# IPS_PilotCape.net
KiCad netlist of a schematic drawn in EAGLE
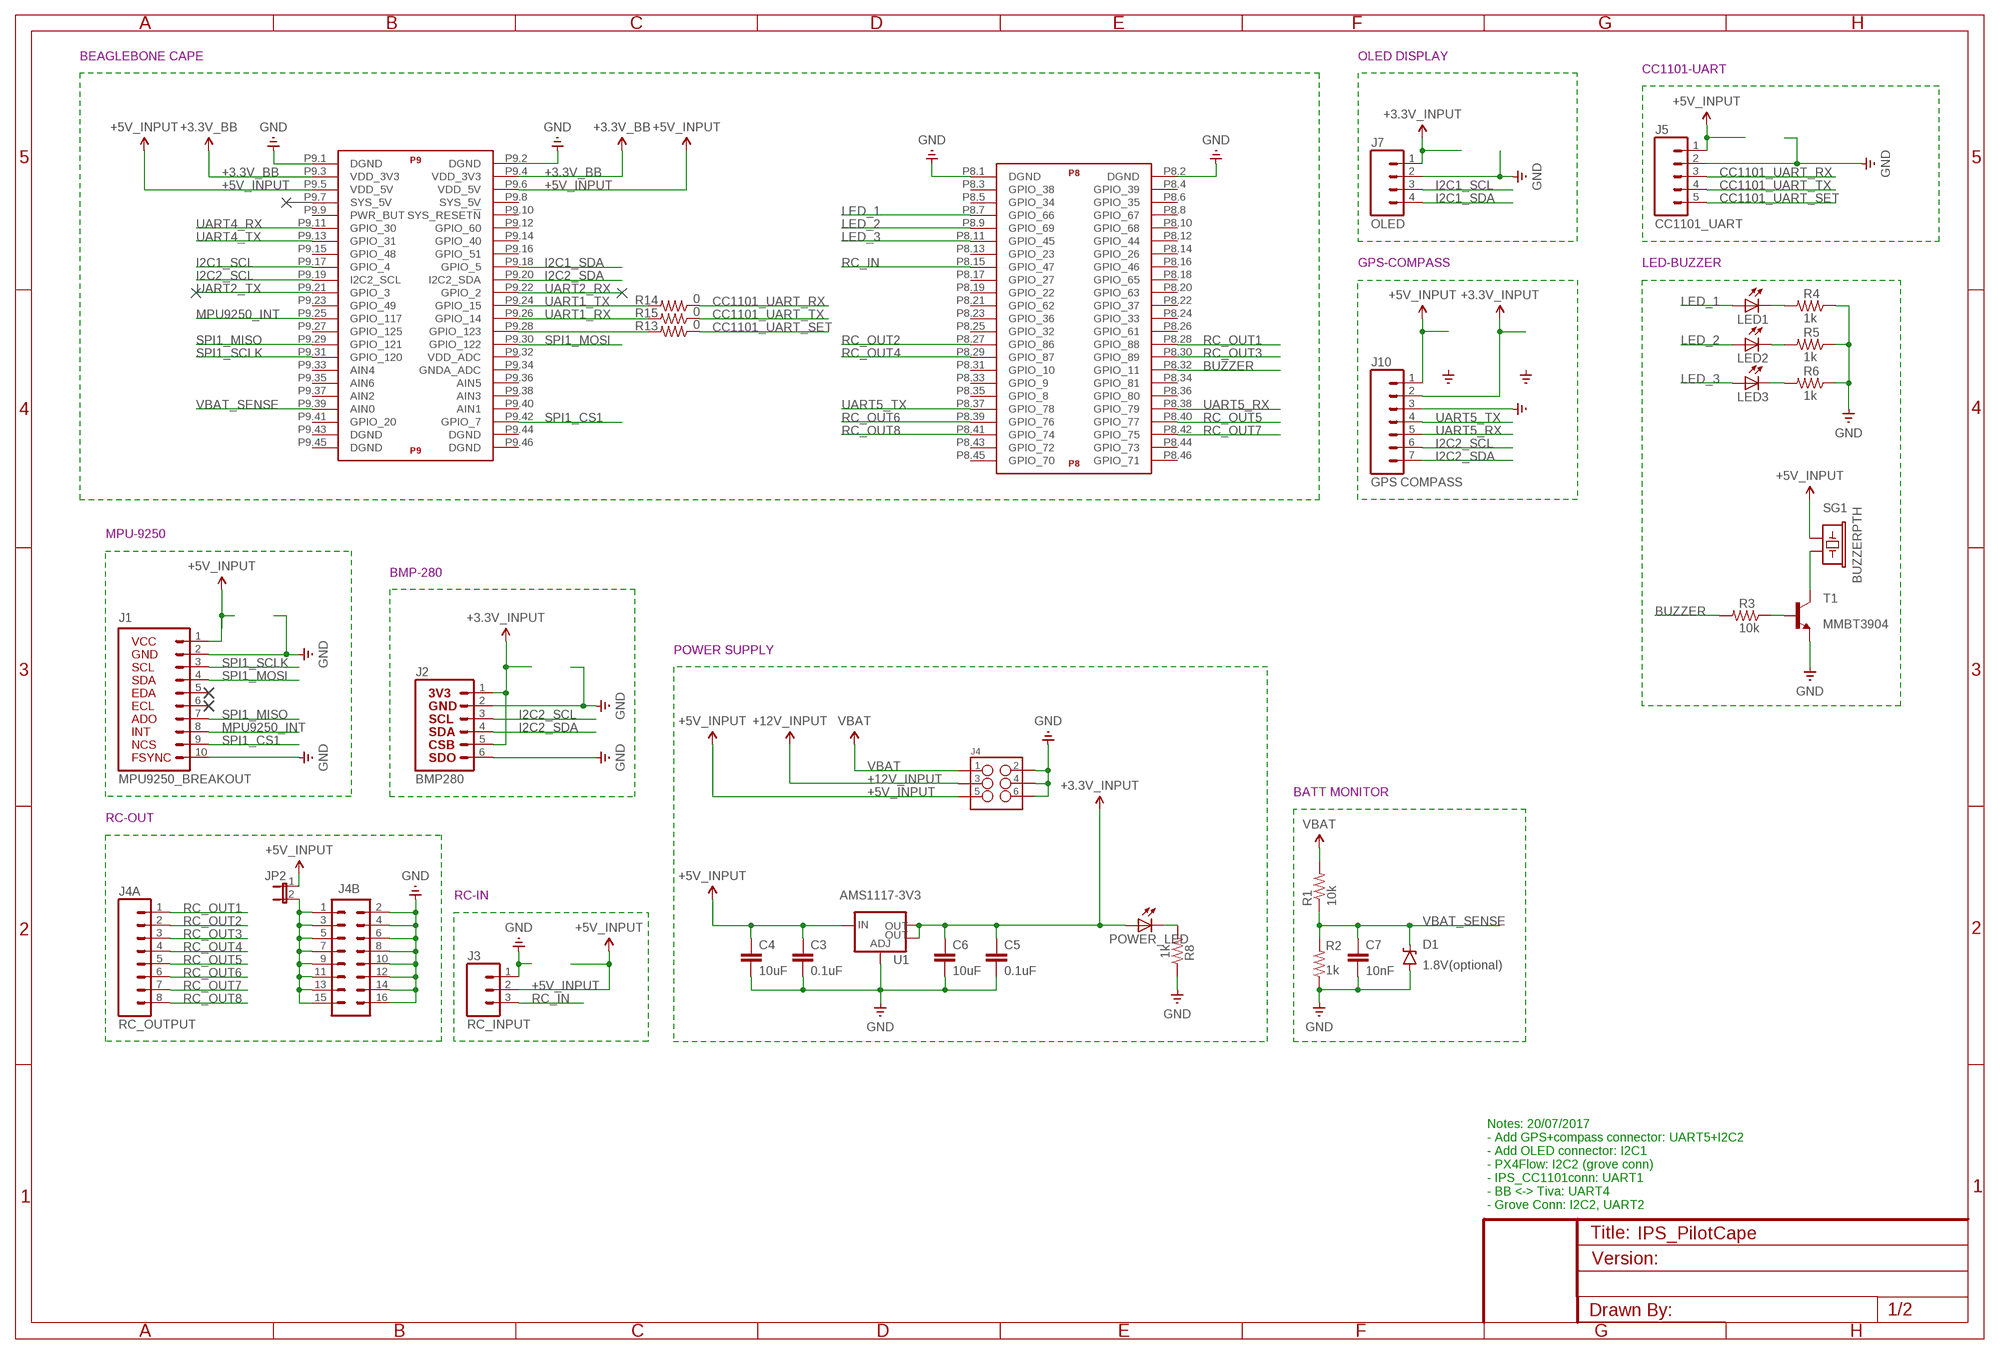
[diagram p0: schematic, sheet 1]
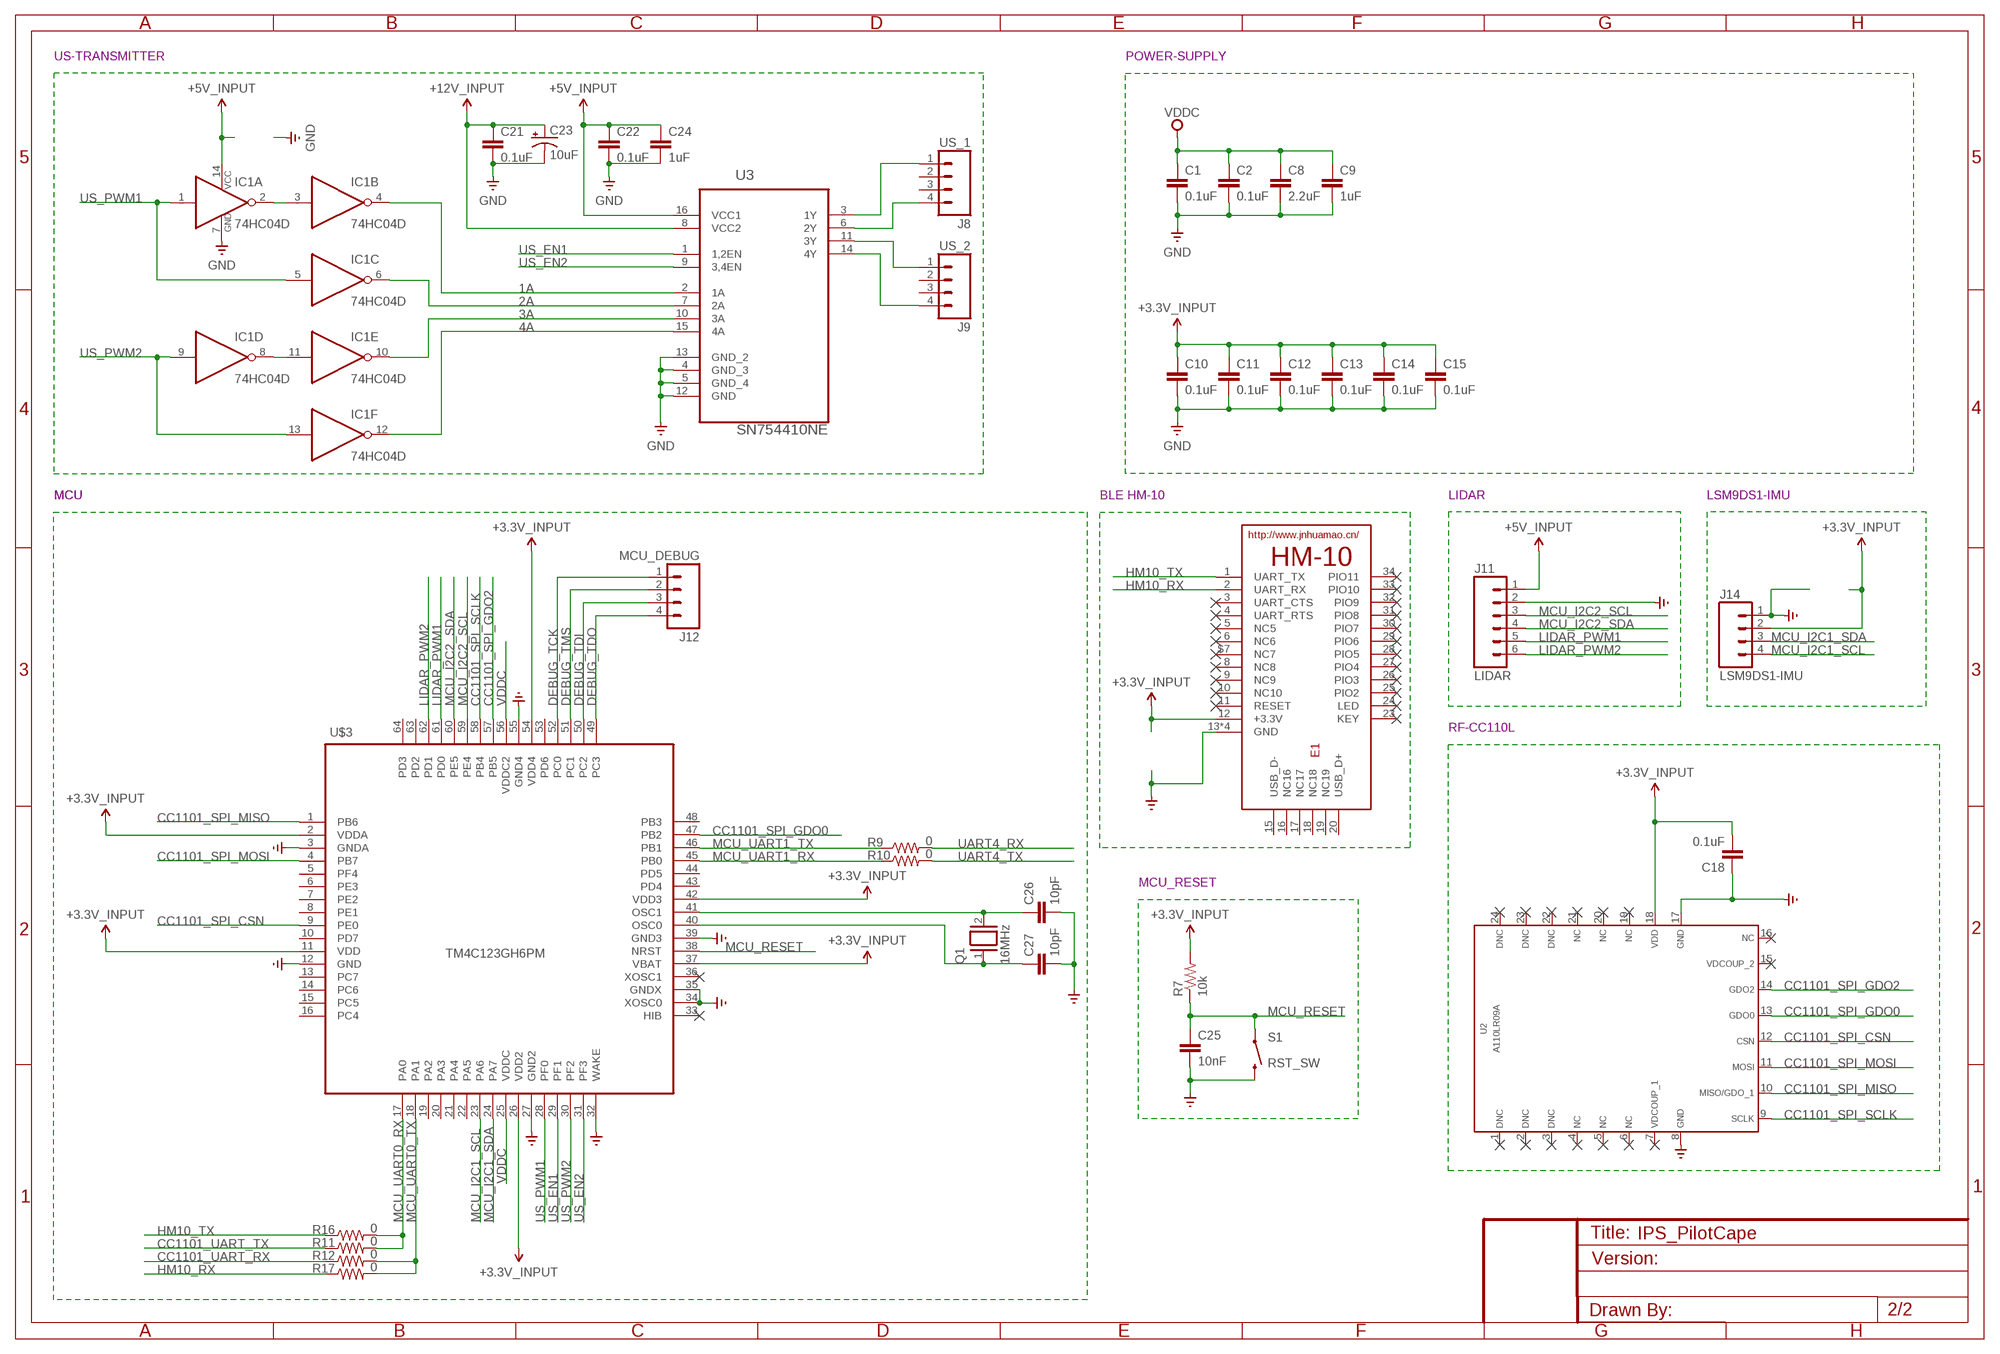
[diagram p1: schematic, sheet 2]

(export (version "E")
  (design (tool "Eeschema 10.0.6"))
  (components
    (comp (ref "C1")
      (value "0.1uF")
      (footprint "eagle-import:0603-CAP")
      (libsource (lib "eagle-import") (part "CAP0603-CAP"))
    )
    (comp (ref "C2")
      (value "0.1uF")
      (footprint "eagle-import:0603-CAP")
      (libsource (lib "eagle-import") (part "CAP0603-CAP"))
    )
    (comp (ref "C8")
      (value "2.2uF")
      (footprint "eagle-import:0603-CAP")
      (libsource (lib "eagle-import") (part "CAP0603-CAP"))
    )
    (comp (ref "C9")
      (value "1uF")
      (footprint "eagle-import:0603-CAP")
      (libsource (lib "eagle-import") (part "CAP0603-CAP"))
    )
    (comp (ref "C10")
      (value "0.1uF")
      (footprint "eagle-import:0603-CAP")
      (libsource (lib "eagle-import") (part "CAP0603-CAP"))
    )
    (comp (ref "C11")
      (value "0.1uF")
      (footprint "eagle-import:0603-CAP")
      (libsource (lib "eagle-import") (part "CAP0603-CAP"))
    )
    (comp (ref "C12")
      (value "0.1uF")
      (footprint "eagle-import:0603-CAP")
      (libsource (lib "eagle-import") (part "CAP0603-CAP"))
    )
    (comp (ref "C13")
      (value "0.1uF")
      (footprint "eagle-import:0603-CAP")
      (libsource (lib "eagle-import") (part "CAP0603-CAP"))
    )
    (comp (ref "C14")
      (value "0.1uF")
      (footprint "eagle-import:0603-CAP")
      (libsource (lib "eagle-import") (part "CAP0603-CAP"))
    )
    (comp (ref "C15")
      (value "0.1uF")
      (footprint "eagle-import:0603-CAP")
      (libsource (lib "eagle-import") (part "CAP0603-CAP"))
    )
    (comp (ref "C18")
      (value "0.1uF")
      (footprint "eagle-import:0603-CAP")
      (libsource (lib "eagle-import") (part "CAP0603-CAP"))
    )
    (comp (ref "C21")
      (value "0.1uF")
      (footprint "eagle-import:0603-CAP")
      (libsource (lib "eagle-import") (part "CAP0603-CAP"))
    )
    (comp (ref "C22")
      (value "0.1uF")
      (footprint "eagle-import:0603-CAP")
      (libsource (lib "eagle-import") (part "CAP0603-CAP"))
    )
    (comp (ref "C23")
      (value "10uF")
      (footprint "eagle-import:EIA3216")
      (libsource (lib "eagle-import") (part "10UF-16V-10%(TANT)"))
    )
    (comp (ref "C24")
      (value "1uF")
      (footprint "eagle-import:0603-CAP")
      (libsource (lib "eagle-import") (part "CAP0603-CAP"))
    )
    (comp (ref "C25")
      (value "10nF")
      (footprint "eagle-import:0603-CAP")
      (libsource (lib "eagle-import") (part "CAP0603-CAP"))
    )
    (comp (ref "C26")
      (value "10pF")
      (footprint "eagle-import:0603-CAP")
      (libsource (lib "eagle-import") (part "CAP0603-CAP"))
    )
    (comp (ref "C27")
      (value "10pF")
      (footprint "eagle-import:0603-CAP")
      (libsource (lib "eagle-import") (part "CAP0603-CAP"))
    )
    (comp (ref "E1")
      (value "HM-10-BOARD")
      (footprint "eagle-import:26.9X13X2.2_BOARD")
      (libsource (lib "eagle-import") (part "HM-10-BOARD"))
    )
    (comp (ref "IC1")
      (value "74HC04D")
      (footprint "eagle-import:SO14")
      (libsource (lib "eagle-import") (part "7404DHC"))
    )
    (comp (ref "J8")
      (value "US_1")
      (footprint "eagle-import:1X04")
      (libsource (lib "eagle-import") (part "M04PTH"))
    )
    (comp (ref "J9")
      (value "US_2")
      (footprint "eagle-import:1X04")
      (libsource (lib "eagle-import") (part "M04PTH"))
    )
    (comp (ref "J11")
      (value "LIDAR")
      (footprint "eagle-import:1X06")
      (libsource (lib "eagle-import") (part "M06SILK_FEMALE_PTH"))
    )
    (comp (ref "J12")
      (value "MCU_DEBUG")
      (footprint "eagle-import:1X04")
      (libsource (lib "eagle-import") (part "M04PTH"))
    )
    (comp (ref "J14")
      (value "LSM9DS1-IMU")
      (footprint "eagle-import:1X04")
      (libsource (lib "eagle-import") (part "M04PTH"))
    )
    (comp (ref "Q1")
      (value "16MHz")
      (footprint "eagle-import:QS")
      (libsource (lib "eagle-import") (part "XTAL/S"))
    )
    (comp (ref "R7")
      (value "10k")
      (footprint "eagle-import:R0603")
      (libsource (lib "eagle-import") (part "R-US_R0603"))
    )
    (comp (ref "R9")
      (value "0")
      (footprint "eagle-import:R0603")
      (libsource (lib "eagle-import") (part "R-US_R0603"))
    )
    (comp (ref "R10")
      (value "0")
      (footprint "eagle-import:R0603")
      (libsource (lib "eagle-import") (part "R-US_R0603"))
    )
    (comp (ref "R11")
      (value "0")
      (footprint "eagle-import:R0603")
      (libsource (lib "eagle-import") (part "R-US_R0603"))
    )
    (comp (ref "R12")
      (value "0")
      (footprint "eagle-import:R0603")
      (libsource (lib "eagle-import") (part "R-US_R0603"))
    )
    (comp (ref "R16")
      (value "0")
      (footprint "eagle-import:R0603")
      (libsource (lib "eagle-import") (part "R-US_R0603"))
    )
    (comp (ref "R17")
      (value "0")
      (footprint "eagle-import:R0603")
      (libsource (lib "eagle-import") (part "R-US_R0603"))
    )
    (comp (ref "S1")
      (value "RST_SW")
      (footprint "eagle-import:TACTILE-SWITCH-1101NE")
      (libsource (lib "eagle-import") (part "SWITCH-MOMENTARY-2SMD-1101NE"))
    )
    (comp (ref "U$3")
      (value "TM4C123GH6PM")
      (footprint "eagle-import:LQPF-64")
      (libsource (lib "eagle-import") (part "TM4C123GH6PM"))
    )
    (comp (ref "U2")
      (value "A110LR09A")
      (footprint "eagle-import:A110LR09A")
      (libsource (lib "eagle-import") (part "A110LR09A"))
    )
    (comp (ref "U3")
      (value "SN754410NE")
      (footprint "eagle-import:DIP254P762X508-16")
      (libsource (lib "eagle-import") (part "SN754410NE"))
    )
    (comp (ref "C3")
      (value "0.1uF")
      (footprint "eagle-import:0603-CAP")
      (libsource (lib "eagle-import") (part "CAP0603-CAP"))
    )
    (comp (ref "C4")
      (value "10uF")
      (footprint "eagle-import:1210")
      (libsource (lib "eagle-import") (part "SparkFun-Passives_CAP1210"))
    )
    (comp (ref "C5")
      (value "0.1uF")
      (footprint "eagle-import:0603-CAP")
      (libsource (lib "eagle-import") (part "CAP0603-CAP"))
    )
    (comp (ref "C6")
      (value "10uF")
      (footprint "eagle-import:1210")
      (libsource (lib "eagle-import") (part "SparkFun-Passives_CAP1210"))
    )
    (comp (ref "C7")
      (value "10nF")
      (footprint "eagle-import:0603-CAP")
      (libsource (lib "eagle-import") (part "CAP0603-CAP"))
    )
    (comp (ref "D1")
      (value "1.8V(optional)")
      (footprint "eagle-import:SOD-323")
      (libsource (lib "eagle-import") (part "DIODE-ZENER3.3V"))
    )
    (comp (ref "J1")
      (value "MPU9250_BREAKOUT")
      (footprint "eagle-import:MPU9250_BREAKOUT")
      (libsource (lib "eagle-import") (part "MPU9250_BREAKOUT"))
    )
    (comp (ref "J2")
      (value "BMP280")
      (footprint "eagle-import:BMP280")
      (libsource (lib "eagle-import") (part "BMP280"))
    )
    (comp (ref "J3")
      (value "RC_INPUT")
      (footprint "eagle-import:1X03")
      (libsource (lib "eagle-import") (part "M03PTH"))
    )
    (comp (ref "J4")
      (value "M03X2NO_SILK")
      (footprint "eagle-import:2X3-NS")
      (libsource (lib "eagle-import") (part "M03X2NO_SILK"))
    )
    (comp (ref "J4A")
      (value "RC_OUTPUT")
      (footprint "eagle-import:1X08")
      (libsource (lib "eagle-import") (part "M08SILK_FEMALE_PTH"))
    )
    (comp (ref "J4B")
      (value "M08X2")
      (footprint "eagle-import:2X8")
      (libsource (lib "eagle-import") (part "M08X2"))
    )
    (comp (ref "J5")
      (value "CC1101_UART")
      (footprint "eagle-import:1X05")
      (libsource (lib "eagle-import") (part "M05PTH"))
    )
    (comp (ref "J7")
      (value "OLED")
      (footprint "eagle-import:1X04")
      (libsource (lib "eagle-import") (part "M04PTH"))
    )
    (comp (ref "J10")
      (value "GPS COMPASS")
      (footprint "eagle-import:1X07")
      (libsource (lib "eagle-import") (part "M07"))
    )
    (comp (ref "JP2")
      (value "JUMPER-2PTH")
      (footprint "eagle-import:1X02")
      (libsource (lib "eagle-import") (part "JUMPER-2PTH"))
    )
    (comp (ref "LED1")
      (value "LEDCHIPLED_0805")
      (footprint "eagle-import:CHIPLED_0805")
      (libsource (lib "eagle-import") (part "LEDCHIPLED_0805"))
    )
    (comp (ref "LED2")
      (value "LEDCHIPLED_0805")
      (footprint "eagle-import:CHIPLED_0805")
      (libsource (lib "eagle-import") (part "LEDCHIPLED_0805"))
    )
    (comp (ref "LED3")
      (value "LEDCHIPLED_0805")
      (footprint "eagle-import:CHIPLED_0805")
      (libsource (lib "eagle-import") (part "LEDCHIPLED_0805"))
    )
    (comp (ref "POWER_LED")
      (value "LEDCHIPLED_0805")
      (footprint "eagle-import:CHIPLED_0805")
      (libsource (lib "eagle-import") (part "LEDCHIPLED_0805"))
    )
    (comp (ref "R1")
      (value "10k")
      (footprint "eagle-import:R0603")
      (libsource (lib "eagle-import") (part "R-US_R0603"))
    )
    (comp (ref "R2")
      (value "1k")
      (footprint "eagle-import:R0603")
      (libsource (lib "eagle-import") (part "R-US_R0603"))
    )
    (comp (ref "R3")
      (value "10k")
      (footprint "eagle-import:R0603")
      (libsource (lib "eagle-import") (part "R-US_R0603"))
    )
    (comp (ref "R4")
      (value "1k")
      (footprint "eagle-import:R0603")
      (libsource (lib "eagle-import") (part "R-US_R0603"))
    )
    (comp (ref "R5")
      (value "1k")
      (footprint "eagle-import:R0603")
      (libsource (lib "eagle-import") (part "R-US_R0603"))
    )
    (comp (ref "R6")
      (value "1k")
      (footprint "eagle-import:R0603")
      (libsource (lib "eagle-import") (part "R-US_R0603"))
    )
    (comp (ref "R8")
      (value "1k")
      (footprint "eagle-import:R0603")
      (libsource (lib "eagle-import") (part "R-US_R0603"))
    )
    (comp (ref "R13")
      (value "0")
      (footprint "eagle-import:R0603")
      (libsource (lib "eagle-import") (part "R-US_R0603"))
    )
    (comp (ref "R14")
      (value "0")
      (footprint "eagle-import:R0603")
      (libsource (lib "eagle-import") (part "R-US_R0603"))
    )
    (comp (ref "R15")
      (value "0")
      (footprint "eagle-import:R0603")
      (libsource (lib "eagle-import") (part "R-US_R0603"))
    )
    (comp (ref "SG1")
      (value "BUZZERPTH")
      (footprint "eagle-import:BUZZER-12MM")
      (libsource (lib "eagle-import") (part "BUZZERPTH"))
    )
    (comp (ref "T1")
      (value "MMBT3904")
      (footprint "eagle-import:SOT23-BEC")
      (libsource (lib "eagle-import") (part "-NPN-SOT23-BECMMBT3904LT1"))
    )
    (comp (ref "U$2")
      (value "BEAGLE_BONE_BLACK_CAPE")
      (footprint "eagle-import:BEAGLE_BONE_BLACK_CAPE")
      (libsource (lib "eagle-import") (part "BEAGLE_BONE_BLACK_CAPE"))
    )
    (comp (ref "U1")
      (value "AMS1117-3V3")
      (footprint "eagle-import:SOT223")
      (libsource (lib "eagle-import") (part "V_REG_LM1117SOT223"))
    )
  )
  (nets
    (net (code "1") (name "+3.3V_BB") (class "Default")
      (node (ref "U$2") (pin "P9.3") (pinfunction "VDD_3V3_P9.3") (pintype "bidirectional"))
      (node (ref "U$2") (pin "P9.4") (pinfunction "VDD_3V3_P9.4") (pintype "bidirectional"))
    )
    (net (code "2") (name "+3.3V_INPUT") (class "Default")
      (node (ref "C10") (pin "1") (pinfunction "1_1") (pintype "passive"))
      (node (ref "C11") (pin "1") (pinfunction "1_1") (pintype "passive"))
      (node (ref "C12") (pin "1") (pinfunction "1_1") (pintype "passive"))
      (node (ref "C13") (pin "1") (pinfunction "1_1") (pintype "passive"))
      (node (ref "C14") (pin "1") (pinfunction "1_1") (pintype "passive"))
      (node (ref "C15") (pin "1") (pinfunction "1_1") (pintype "passive"))
      (node (ref "C18") (pin "2") (pinfunction "2_2") (pintype "passive"))
      (node (ref "C5") (pin "1") (pinfunction "1_1") (pintype "passive"))
      (node (ref "C6") (pin "1") (pinfunction "1_1") (pintype "passive"))
      (node (ref "E1") (pin "12") (pinfunction "+3.3V_12") (pintype "bidirectional"))
      (node (ref "J10") (pin "2") (pinfunction "2_2") (pintype "passive"))
      (node (ref "J14") (pin "2") (pinfunction "2_2") (pintype "passive"))
      (node (ref "J2") (pin "1") (pinfunction "1_1") (pintype "passive"))
      (node (ref "J2") (pin "5") (pinfunction "5_5") (pintype "passive"))
      (node (ref "J7") (pin "1") (pinfunction "1_1") (pintype "passive"))
      (node (ref "POWER_LED") (pin "A") (pinfunction "A_A") (pintype "passive"))
      (node (ref "R7") (pin "2") (pinfunction "2_2") (pintype "passive"))
      (node (ref "U$3") (pin "11") (pinfunction "VDD_11") (pintype "bidirectional"))
      (node (ref "U$3") (pin "2") (pinfunction "VDDA_2") (pintype "bidirectional"))
      (node (ref "U$3") (pin "26") (pinfunction "VDD2_26") (pintype "bidirectional"))
      (node (ref "U$3") (pin "37") (pinfunction "VBAT_37") (pintype "bidirectional"))
      (node (ref "U$3") (pin "42") (pinfunction "VDD3_42") (pintype "bidirectional"))
      (node (ref "U$3") (pin "54") (pinfunction "VDD4_54") (pintype "bidirectional"))
      (node (ref "U1") (pin "2") (pinfunction "OUT_2") (pintype "output"))
      (node (ref "U1") (pin "4") (pinfunction "OUT_4") (pintype "output"))
      (node (ref "U2") (pin "18") (pinfunction "P$18_18") (pintype "bidirectional"))
    )
    (net (code "3") (name "+5V_INPUT") (class "Default")
      (node (ref "C22") (pin "1") (pinfunction "1_1") (pintype "passive"))
      (node (ref "C24") (pin "1") (pinfunction "1_1") (pintype "passive"))
      (node (ref "C3") (pin "1") (pinfunction "1_1") (pintype "passive"))
      (node (ref "C4") (pin "1") (pinfunction "1_1") (pintype "passive"))
      (node (ref "IC1") (pin "14") (pinfunction "VCC_14") (pintype "power_in"))
      (node (ref "J1") (pin "1") (pinfunction "1_1") (pintype "passive"))
      (node (ref "J10") (pin "1") (pinfunction "1_1") (pintype "passive"))
      (node (ref "J11") (pin "1") (pinfunction "1_1") (pintype "passive"))
      (node (ref "J3") (pin "2") (pinfunction "2_2") (pintype "passive"))
      (node (ref "J4") (pin "5") (pinfunction "5_5") (pintype "bidirectional"))
      (node (ref "J5") (pin "1") (pinfunction "1_1") (pintype "passive"))
      (node (ref "JP2") (pin "1") (pinfunction "1_1") (pintype "passive"))
      (node (ref "SG1") (pin "+") (pinfunction "1_+") (pintype "passive"))
      (node (ref "U$2") (pin "P9.5") (pinfunction "VDD_5V_P9.5") (pintype "bidirectional"))
      (node (ref "U$2") (pin "P9.6") (pinfunction "VDD_5V_P9.6") (pintype "bidirectional"))
      (node (ref "U1") (pin "3") (pinfunction "IN_3") (pintype "input"))
      (node (ref "U3") (pin "16") (pinfunction "VCC1_16") (pintype "power_in"))
    )
    (net (code "4") (name "+12V_INPUT") (class "Default")
      (node (ref "C21") (pin "1") (pinfunction "1_1") (pintype "passive"))
      (node (ref "C23") (pin "A") (pinfunction "+_A") (pintype "passive"))
      (node (ref "J4") (pin "3") (pinfunction "3_3") (pintype "bidirectional"))
      (node (ref "U3") (pin "8") (pinfunction "VCC2_8") (pintype "power_in"))
    )
    (net (code "5") (name "1A") (class "Default")
      (node (ref "IC1") (pin "4") (pinfunction "O_4") (pintype "output"))
      (node (ref "U3") (pin "2") (pinfunction "1A_2") (pintype "input"))
    )
    (net (code "6") (name "2A") (class "Default")
      (node (ref "IC1") (pin "6") (pinfunction "O_6") (pintype "output"))
      (node (ref "U3") (pin "7") (pinfunction "2A_7") (pintype "input"))
    )
    (net (code "7") (name "3A") (class "Default")
      (node (ref "IC1") (pin "10") (pinfunction "O_10") (pintype "output"))
      (node (ref "U3") (pin "10") (pinfunction "3A_10") (pintype "input"))
    )
    (net (code "8") (name "4A") (class "Default")
      (node (ref "IC1") (pin "12") (pinfunction "O_12") (pintype "output"))
      (node (ref "U3") (pin "15") (pinfunction "4A_15") (pintype "input"))
    )
    (net (code "9") (name "BUZZER") (class "Default")
      (node (ref "R3") (pin "2") (pinfunction "2_2") (pintype "passive"))
      (node (ref "U$2") (pin "P8.32") (pinfunction "GPIO_11_P8.32") (pintype "bidirectional"))
    )
    (net (code "10") (name "CC1101_SPI_CSN") (class "Default")
      (node (ref "U$3") (pin "9") (pinfunction "PE0_9") (pintype "bidirectional"))
      (node (ref "U2") (pin "12") (pinfunction "P$12_12") (pintype "bidirectional"))
    )
    (net (code "11") (name "CC1101_SPI_GDO0") (class "Default")
      (node (ref "U$3") (pin "47") (pinfunction "PB2_47") (pintype "bidirectional"))
      (node (ref "U2") (pin "13") (pinfunction "P$13_13") (pintype "bidirectional"))
    )
    (net (code "12") (name "CC1101_SPI_GDO2") (class "Default")
      (node (ref "U$3") (pin "57") (pinfunction "PB5_57") (pintype "bidirectional"))
      (node (ref "U2") (pin "14") (pinfunction "P$14_14") (pintype "bidirectional"))
    )
    (net (code "13") (name "CC1101_SPI_MISO") (class "Default")
      (node (ref "U$3") (pin "1") (pinfunction "PB6_1") (pintype "bidirectional"))
      (node (ref "U2") (pin "10") (pinfunction "P$10_10") (pintype "bidirectional"))
    )
    (net (code "14") (name "CC1101_SPI_MOSI") (class "Default")
      (node (ref "U$3") (pin "4") (pinfunction "PB7_4") (pintype "bidirectional"))
      (node (ref "U2") (pin "11") (pinfunction "P$11_11") (pintype "bidirectional"))
    )
    (net (code "15") (name "CC1101_SPI_SCLK") (class "Default")
      (node (ref "U$3") (pin "58") (pinfunction "PB4_58") (pintype "bidirectional"))
      (node (ref "U2") (pin "9") (pinfunction "P$9_9") (pintype "bidirectional"))
    )
    (net (code "16") (name "CC1101_UART_RX") (class "Default")
      (node (ref "J5") (pin "3") (pinfunction "3_3") (pintype "passive"))
      (node (ref "R12") (pin "1") (pinfunction "1_1") (pintype "passive"))
      (node (ref "R14") (pin "1") (pinfunction "1_1") (pintype "passive"))
    )
    (net (code "17") (name "CC1101_UART_SET") (class "Default")
      (node (ref "J5") (pin "5") (pinfunction "5_5") (pintype "passive"))
      (node (ref "R13") (pin "1") (pinfunction "1_1") (pintype "passive"))
    )
    (net (code "18") (name "CC1101_UART_TX") (class "Default")
      (node (ref "J5") (pin "4") (pinfunction "4_4") (pintype "passive"))
      (node (ref "R11") (pin "1") (pinfunction "1_1") (pintype "passive"))
      (node (ref "R15") (pin "1") (pinfunction "1_1") (pintype "passive"))
    )
    (net (code "19") (name "DEBUG_TCK") (class "Default")
      (node (ref "J12") (pin "1") (pinfunction "1_1") (pintype "passive"))
      (node (ref "U$3") (pin "52") (pinfunction "PC0_52") (pintype "bidirectional"))
    )
    (net (code "20") (name "DEBUG_TDI") (class "Default")
      (node (ref "J12") (pin "3") (pinfunction "3_3") (pintype "passive"))
      (node (ref "U$3") (pin "50") (pinfunction "PC2_50") (pintype "bidirectional"))
    )
    (net (code "21") (name "DEBUG_TDO") (class "Default")
      (node (ref "J12") (pin "4") (pinfunction "4_4") (pintype "passive"))
      (node (ref "U$3") (pin "49") (pinfunction "PC3_49") (pintype "bidirectional"))
    )
    (net (code "22") (name "DEBUG_TMS") (class "Default")
      (node (ref "J12") (pin "2") (pinfunction "2_2") (pintype "passive"))
      (node (ref "U$3") (pin "51") (pinfunction "PC1_51") (pintype "bidirectional"))
    )
    (net (code "23") (name "GND") (class "Default")
      (node (ref "C1") (pin "2") (pinfunction "2_2") (pintype "passive"))
      (node (ref "C10") (pin "2") (pinfunction "2_2") (pintype "passive"))
      (node (ref "C11") (pin "2") (pinfunction "2_2") (pintype "passive"))
      (node (ref "C12") (pin "2") (pinfunction "2_2") (pintype "passive"))
      (node (ref "C13") (pin "2") (pinfunction "2_2") (pintype "passive"))
      (node (ref "C14") (pin "2") (pinfunction "2_2") (pintype "passive"))
      (node (ref "C15") (pin "2") (pinfunction "2_2") (pintype "passive"))
      (node (ref "C18") (pin "1") (pinfunction "1_1") (pintype "passive"))
      (node (ref "C2") (pin "2") (pinfunction "2_2") (pintype "passive"))
      (node (ref "C21") (pin "2") (pinfunction "2_2") (pintype "passive"))
      (node (ref "C22") (pin "2") (pinfunction "2_2") (pintype "passive"))
      (node (ref "C23") (pin "C") (pinfunction "-_C") (pintype "passive"))
      (node (ref "C24") (pin "2") (pinfunction "2_2") (pintype "passive"))
      (node (ref "C25") (pin "2") (pinfunction "2_2") (pintype "passive"))
      (node (ref "C26") (pin "2") (pinfunction "2_2") (pintype "passive"))
      (node (ref "C27") (pin "2") (pinfunction "2_2") (pintype "passive"))
      (node (ref "C3") (pin "2") (pinfunction "2_2") (pintype "passive"))
      (node (ref "C4") (pin "2") (pinfunction "2_2") (pintype "passive"))
      (node (ref "C5") (pin "2") (pinfunction "2_2") (pintype "passive"))
      (node (ref "C6") (pin "2") (pinfunction "2_2") (pintype "passive"))
      (node (ref "C7") (pin "2") (pinfunction "2_2") (pintype "passive"))
      (node (ref "C8") (pin "2") (pinfunction "2_2") (pintype "passive"))
      (node (ref "C9") (pin "2") (pinfunction "2_2") (pintype "passive"))
      (node (ref "D1") (pin "A") (pinfunction "A_A") (pintype "passive"))
      (node (ref "E1") (pin "13") (pinfunction "GND_13") (pintype "bidirectional"))
      (node (ref "E1") (pin "14") (pinfunction "GND_14") (pintype "bidirectional"))
      (node (ref "E1") (pin "21") (pinfunction "GND_21") (pintype "bidirectional"))
      (node (ref "E1") (pin "22") (pinfunction "GND_22") (pintype "bidirectional"))
      (node (ref "IC1") (pin "7") (pinfunction "GND_7") (pintype "power_in"))
      (node (ref "J1") (pin "10") (pinfunction "10_10") (pintype "passive"))
      (node (ref "J1") (pin "2") (pinfunction "2_2") (pintype "passive"))
      (node (ref "J10") (pin "3") (pinfunction "3_3") (pintype "passive"))
      (node (ref "J11") (pin "2") (pinfunction "2_2") (pintype "passive"))
      (node (ref "J14") (pin "1") (pinfunction "1_1") (pintype "passive"))
      (node (ref "J2") (pin "2") (pinfunction "2_2") (pintype "passive"))
      (node (ref "J2") (pin "6") (pinfunction "6_6") (pintype "passive"))
      (node (ref "J3") (pin "1") (pinfunction "1_1") (pintype "passive"))
      (node (ref "J4") (pin "2") (pinfunction "2_2") (pintype "bidirectional"))
      (node (ref "J4") (pin "4") (pinfunction "4_4") (pintype "bidirectional"))
      (node (ref "J4") (pin "6") (pinfunction "6_6") (pintype "bidirectional"))
      (node (ref "J4B") (pin "10") (pinfunction "10_10") (pintype "passive"))
      (node (ref "J4B") (pin "12") (pinfunction "12_12") (pintype "passive"))
      (node (ref "J4B") (pin "14") (pinfunction "14_14") (pintype "passive"))
      (node (ref "J4B") (pin "16") (pinfunction "16_16") (pintype "passive"))
      (node (ref "J4B") (pin "2") (pinfunction "2_2") (pintype "passive"))
      (node (ref "J4B") (pin "4") (pinfunction "4_4") (pintype "passive"))
      (node (ref "J4B") (pin "6") (pinfunction "6_6") (pintype "passive"))
      (node (ref "J4B") (pin "8") (pinfunction "8_8") (pintype "passive"))
      (node (ref "J5") (pin "2") (pinfunction "2_2") (pintype "passive"))
      (node (ref "J7") (pin "2") (pinfunction "2_2") (pintype "passive"))
      (node (ref "R2") (pin "1") (pinfunction "1_1") (pintype "passive"))
      (node (ref "R4") (pin "1") (pinfunction "1_1") (pintype "passive"))
      (node (ref "R5") (pin "1") (pinfunction "1_1") (pintype "passive"))
      (node (ref "R6") (pin "1") (pinfunction "1_1") (pintype "passive"))
      (node (ref "R8") (pin "1") (pinfunction "1_1") (pintype "passive"))
      (node (ref "S1") (pin "2") (pinfunction "2_2") (pintype "passive"))
      (node (ref "T1") (pin "E") (pinfunction "E_E") (pintype "passive"))
      (node (ref "U$2") (pin "P8.1") (pinfunction "DGND_P8.1") (pintype "bidirectional"))
      (node (ref "U$2") (pin "P8.2") (pinfunction "DGND_P8.2") (pintype "bidirectional"))
      (node (ref "U$2") (pin "P9.1") (pinfunction "DGND_P9.1") (pintype "bidirectional"))
      (node (ref "U$2") (pin "P9.2") (pinfunction "DGND_P9.2") (pintype "bidirectional"))
      (node (ref "U$3") (pin "12") (pinfunction "GND_12") (pintype "bidirectional"))
      (node (ref "U$3") (pin "27") (pinfunction "GND2_27") (pintype "bidirectional"))
      (node (ref "U$3") (pin "3") (pinfunction "GNDA_3") (pintype "bidirectional"))
      (node (ref "U$3") (pin "32") (pinfunction "WAKE_32") (pintype "bidirectional"))
      (node (ref "U$3") (pin "34") (pinfunction "XOSC0_34") (pintype "bidirectional"))
      (node (ref "U$3") (pin "35") (pinfunction "GNDX_35") (pintype "bidirectional"))
      (node (ref "U$3") (pin "39") (pinfunction "GND3_39") (pintype "bidirectional"))
      (node (ref "U$3") (pin "55") (pinfunction "GND4_55") (pintype "bidirectional"))
      (node (ref "U1") (pin "1") (pinfunction "ADJ_1") (pintype "input"))
      (node (ref "U2") (pin "17") (pinfunction "P$17_17") (pintype "bidirectional"))
      (node (ref "U2") (pin "8") (pinfunction "P$8_8") (pintype "bidirectional"))
      (node (ref "U3") (pin "12") (pinfunction "GND_12") (pintype "passive"))
      (node (ref "U3") (pin "13") (pinfunction "GND_2_13") (pintype "passive"))
      (node (ref "U3") (pin "4") (pinfunction "GND_3_4") (pintype "passive"))
      (node (ref "U3") (pin "5") (pinfunction "GND_4_5") (pintype "passive"))
    )
    (net (code "24") (name "HM10_RX") (class "Default")
      (node (ref "E1") (pin "2") (pinfunction "UART_RX_2") (pintype "bidirectional"))
      (node (ref "R17") (pin "1") (pinfunction "1_1") (pintype "passive"))
    )
    (net (code "25") (name "HM10_TX") (class "Default")
      (node (ref "E1") (pin "1") (pinfunction "UART_TX_1") (pintype "bidirectional"))
      (node (ref "R16") (pin "1") (pinfunction "1_1") (pintype "passive"))
    )
    (net (code "26") (name "I2C1_SCL") (class "Default")
      (node (ref "J7") (pin "3") (pinfunction "3_3") (pintype "passive"))
      (node (ref "U$2") (pin "P9.17") (pinfunction "GPIO_4_P9.17") (pintype "bidirectional"))
    )
    (net (code "27") (name "I2C1_SDA") (class "Default")
      (node (ref "J7") (pin "4") (pinfunction "4_4") (pintype "passive"))
      (node (ref "U$2") (pin "P9.18") (pinfunction "GPIO_5_P9.18") (pintype "bidirectional"))
    )
    (net (code "28") (name "I2C2_SCL") (class "Default")
      (node (ref "J10") (pin "6") (pinfunction "6_6") (pintype "passive"))
      (node (ref "J2") (pin "3") (pinfunction "3_3") (pintype "passive"))
      (node (ref "U$2") (pin "P9.19") (pinfunction "I2C2_SCL_P9.19") (pintype "bidirectional"))
    )
    (net (code "29") (name "I2C2_SDA") (class "Default")
      (node (ref "J10") (pin "7") (pinfunction "7_7") (pintype "passive"))
      (node (ref "J2") (pin "4") (pinfunction "4_4") (pintype "passive"))
      (node (ref "U$2") (pin "P9.20") (pinfunction "I2C2_SDA_P9.20") (pintype "bidirectional"))
    )
    (net (code "30") (name "LED_1") (class "Default")
      (node (ref "LED1") (pin "A") (pinfunction "A_A") (pintype "passive"))
      (node (ref "U$2") (pin "P8.7") (pinfunction "GPIO_66_P8.7") (pintype "bidirectional"))
    )
    (net (code "31") (name "LED_2") (class "Default")
      (node (ref "LED2") (pin "A") (pinfunction "A_A") (pintype "passive"))
      (node (ref "U$2") (pin "P8.9") (pinfunction "GPIO_69_P8.9") (pintype "bidirectional"))
    )
    (net (code "32") (name "LED_3") (class "Default")
      (node (ref "LED3") (pin "A") (pinfunction "A_A") (pintype "passive"))
      (node (ref "U$2") (pin "P8.11") (pinfunction "GPIO_45_P8.11") (pintype "bidirectional"))
    )
    (net (code "33") (name "LIDAR_PWM1") (class "Default")
      (node (ref "J11") (pin "5") (pinfunction "5_5") (pintype "passive"))
      (node (ref "U$3") (pin "61") (pinfunction "PD0_61") (pintype "bidirectional"))
    )
    (net (code "34") (name "LIDAR_PWM2") (class "Default")
      (node (ref "J11") (pin "6") (pinfunction "6_6") (pintype "passive"))
      (node (ref "U$3") (pin "62") (pinfunction "PD1_62") (pintype "bidirectional"))
    )
    (net (code "35") (name "MCU_I2C1_SCL") (class "Default")
      (node (ref "J14") (pin "4") (pinfunction "4_4") (pintype "passive"))
      (node (ref "U$3") (pin "23") (pinfunction "PA6_23") (pintype "bidirectional"))
    )
    (net (code "36") (name "MCU_I2C1_SDA") (class "Default")
      (node (ref "J14") (pin "3") (pinfunction "3_3") (pintype "passive"))
      (node (ref "U$3") (pin "24") (pinfunction "PA7_24") (pintype "bidirectional"))
    )
    (net (code "37") (name "MCU_I2C2_SCL") (class "Default")
      (node (ref "J11") (pin "3") (pinfunction "3_3") (pintype "passive"))
      (node (ref "U$3") (pin "59") (pinfunction "PE4_59") (pintype "bidirectional"))
    )
    (net (code "38") (name "MCU_I2C2_SDA") (class "Default")
      (node (ref "J11") (pin "4") (pinfunction "4_4") (pintype "passive"))
      (node (ref "U$3") (pin "60") (pinfunction "PE5_60") (pintype "bidirectional"))
    )
    (net (code "39") (name "MCU_RESET") (class "Default")
      (node (ref "C25") (pin "1") (pinfunction "1_1") (pintype "passive"))
      (node (ref "R7") (pin "1") (pinfunction "1_1") (pintype "passive"))
      (node (ref "S1") (pin "1") (pinfunction "1_1") (pintype "passive"))
      (node (ref "U$3") (pin "38") (pinfunction "NRST_38") (pintype "bidirectional"))
    )
    (net (code "40") (name "MCU_UART0_RX") (class "Default")
      (node (ref "R11") (pin "2") (pinfunction "2_2") (pintype "passive"))
      (node (ref "R16") (pin "2") (pinfunction "2_2") (pintype "passive"))
      (node (ref "U$3") (pin "17") (pinfunction "PA0_17") (pintype "bidirectional"))
    )
    (net (code "41") (name "MCU_UART0_TX") (class "Default")
      (node (ref "R12") (pin "2") (pinfunction "2_2") (pintype "passive"))
      (node (ref "R17") (pin "2") (pinfunction "2_2") (pintype "passive"))
      (node (ref "U$3") (pin "18") (pinfunction "PA1_18") (pintype "bidirectional"))
    )
    (net (code "42") (name "MCU_UART1_RX") (class "Default")
      (node (ref "R10") (pin "1") (pinfunction "1_1") (pintype "passive"))
      (node (ref "U$3") (pin "45") (pinfunction "PB0_45") (pintype "bidirectional"))
    )
    (net (code "43") (name "MCU_UART1_TX") (class "Default")
      (node (ref "R9") (pin "1") (pinfunction "1_1") (pintype "passive"))
      (node (ref "U$3") (pin "46") (pinfunction "PB1_46") (pintype "bidirectional"))
    )
    (net (code "44") (name "MPU9250_INT") (class "Default")
      (node (ref "J1") (pin "8") (pinfunction "8_8") (pintype "passive"))
      (node (ref "U$2") (pin "P9.25") (pinfunction "GPIO_117_P9.25") (pintype "bidirectional"))
    )
    (net (code "45") (name "Net-(IC1A-O)") (class "Default")
      (node (ref "IC1") (pin "2") (pinfunction "O_2") (pintype "output"))
      (node (ref "IC1") (pin "3") (pinfunction "I_3") (pintype "input"))
    )
    (net (code "46") (name "Net-(IC1D-O)") (class "Default")
      (node (ref "IC1") (pin "11") (pinfunction "I_11") (pintype "input"))
      (node (ref "IC1") (pin "8") (pinfunction "O_8") (pintype "output"))
    )
    (net (code "47") (name "Net-(J4B-Pad1)") (class "Default")
      (node (ref "J4B") (pin "1") (pinfunction "1_1") (pintype "passive"))
      (node (ref "J4B") (pin "11") (pinfunction "11_11") (pintype "passive"))
      (node (ref "J4B") (pin "13") (pinfunction "13_13") (pintype "passive"))
      (node (ref "J4B") (pin "15") (pinfunction "15_15") (pintype "passive"))
      (node (ref "J4B") (pin "3") (pinfunction "3_3") (pintype "passive"))
      (node (ref "J4B") (pin "5") (pinfunction "5_5") (pintype "passive"))
      (node (ref "J4B") (pin "7") (pinfunction "7_7") (pintype "passive"))
      (node (ref "J4B") (pin "9") (pinfunction "9_9") (pintype "passive"))
      (node (ref "JP2") (pin "2") (pinfunction "2_2") (pintype "passive"))
    )
    (net (code "48") (name "Net-(LED1-PadC)") (class "Default")
      (node (ref "LED1") (pin "C") (pinfunction "C_C") (pintype "passive"))
      (node (ref "R4") (pin "2") (pinfunction "2_2") (pintype "passive"))
    )
    (net (code "49") (name "Net-(LED2-PadC)") (class "Default")
      (node (ref "LED2") (pin "C") (pinfunction "C_C") (pintype "passive"))
      (node (ref "R5") (pin "2") (pinfunction "2_2") (pintype "passive"))
    )
    (net (code "50") (name "Net-(LED3-PadC)") (class "Default")
      (node (ref "LED3") (pin "C") (pinfunction "C_C") (pintype "passive"))
      (node (ref "R6") (pin "2") (pinfunction "2_2") (pintype "passive"))
    )
    (net (code "51") (name "Net-(POWER_LED-PadC)") (class "Default")
      (node (ref "POWER_LED") (pin "C") (pinfunction "C_C") (pintype "passive"))
      (node (ref "R8") (pin "2") (pinfunction "2_2") (pintype "passive"))
    )
    (net (code "52") (name "Net-(R3-Pad1)") (class "Default")
      (node (ref "R3") (pin "1") (pinfunction "1_1") (pintype "passive"))
      (node (ref "T1") (pin "B") (pinfunction "B_B") (pintype "passive"))
    )
    (net (code "53") (name "Net-(SG1-2)") (class "Default")
      (node (ref "SG1") (pin "-") (pinfunction "2_-") (pintype "passive"))
      (node (ref "T1") (pin "C") (pinfunction "C_C") (pintype "passive"))
    )
    (net (code "54") (name "Net-(U$2B-GPIO_123)") (class "Default")
      (node (ref "R13") (pin "2") (pinfunction "2_2") (pintype "passive"))
      (node (ref "U$2") (pin "P9.28") (pinfunction "GPIO_123_P9.28") (pintype "bidirectional"))
    )
    (net (code "55") (name "Net-(U$3-OSC0)") (class "Default")
      (node (ref "C27") (pin "1") (pinfunction "1_1") (pintype "passive"))
      (node (ref "Q1") (pin "1") (pinfunction "1_1") (pintype "passive"))
      (node (ref "U$3") (pin "40") (pinfunction "OSC0_40") (pintype "bidirectional"))
    )
    (net (code "56") (name "Net-(U$3-OSC1)") (class "Default")
      (node (ref "C26") (pin "1") (pinfunction "1_1") (pintype "passive"))
      (node (ref "Q1") (pin "2") (pinfunction "2_2") (pintype "passive"))
      (node (ref "U$3") (pin "41") (pinfunction "OSC1_41") (pintype "bidirectional"))
    )
    (net (code "57") (name "Net-(U3-1Y)") (class "Default")
      (node (ref "J8") (pin "1") (pinfunction "1_1") (pintype "passive"))
      (node (ref "U3") (pin "3") (pinfunction "1Y_3") (pintype "output"))
    )
    (net (code "58") (name "Net-(U3-2Y)") (class "Default")
      (node (ref "J8") (pin "4") (pinfunction "4_4") (pintype "passive"))
      (node (ref "U3") (pin "6") (pinfunction "2Y_6") (pintype "output"))
    )
    (net (code "59") (name "Net-(U3-3Y)") (class "Default")
      (node (ref "J9") (pin "1") (pinfunction "1_1") (pintype "passive"))
      (node (ref "U3") (pin "11") (pinfunction "3Y_11") (pintype "output"))
    )
    (net (code "60") (name "Net-(U3-4Y)") (class "Default")
      (node (ref "J9") (pin "4") (pinfunction "4_4") (pintype "passive"))
      (node (ref "U3") (pin "14") (pinfunction "4Y_14") (pintype "output"))
    )
    (net (code "61") (name "RC_IN") (class "Default")
      (node (ref "J3") (pin "3") (pinfunction "3_3") (pintype "passive"))
      (node (ref "U$2") (pin "P8.15") (pinfunction "GPIO_47_P8.15") (pintype "bidirectional"))
    )
    (net (code "62") (name "RC_OUT1") (class "Default")
      (node (ref "J4A") (pin "1") (pinfunction "1_1") (pintype "passive"))
      (node (ref "U$2") (pin "P8.28") (pinfunction "GPIO_88_P8.28") (pintype "bidirectional"))
    )
    (net (code "63") (name "RC_OUT2") (class "Default")
      (node (ref "J4A") (pin "2") (pinfunction "2_2") (pintype "passive"))
      (node (ref "U$2") (pin "P8.27") (pinfunction "GPIO_86_P8.27") (pintype "bidirectional"))
    )
    (net (code "64") (name "RC_OUT3") (class "Default")
      (node (ref "J4A") (pin "3") (pinfunction "3_3") (pintype "passive"))
      (node (ref "U$2") (pin "P8.30") (pinfunction "GPIO_89_P8.30") (pintype "bidirectional"))
    )
    (net (code "65") (name "RC_OUT4") (class "Default")
      (node (ref "J4A") (pin "4") (pinfunction "4_4") (pintype "passive"))
      (node (ref "U$2") (pin "P8.29") (pinfunction "GPIO_87_P8.29") (pintype "bidirectional"))
    )
    (net (code "66") (name "RC_OUT5") (class "Default")
      (node (ref "J4A") (pin "5") (pinfunction "5_5") (pintype "passive"))
      (node (ref "U$2") (pin "P8.40") (pinfunction "GPIO_77_P8.40") (pintype "bidirectional"))
    )
    (net (code "67") (name "RC_OUT6") (class "Default")
      (node (ref "J4A") (pin "6") (pinfunction "6_6") (pintype "passive"))
      (node (ref "U$2") (pin "P8.39") (pinfunction "GPIO_76_P8.39") (pintype "bidirectional"))
    )
    (net (code "68") (name "RC_OUT7") (class "Default")
      (node (ref "J4A") (pin "7") (pinfunction "7_7") (pintype "passive"))
      (node (ref "U$2") (pin "P8.42") (pinfunction "GPIO_75_P8.42") (pintype "bidirectional"))
    )
    (net (code "69") (name "RC_OUT8") (class "Default")
      (node (ref "J4A") (pin "8") (pinfunction "8_8") (pintype "passive"))
      (node (ref "U$2") (pin "P8.41") (pinfunction "GPIO_74_P8.41") (pintype "bidirectional"))
    )
    (net (code "70") (name "SPI1_CS1") (class "Default")
      (node (ref "J1") (pin "9") (pinfunction "9_9") (pintype "passive"))
      (node (ref "U$2") (pin "P9.42") (pinfunction "GPIO_7_P9.42") (pintype "bidirectional"))
    )
    (net (code "71") (name "SPI1_MISO") (class "Default")
      (node (ref "J1") (pin "7") (pinfunction "7_7") (pintype "passive"))
      (node (ref "U$2") (pin "P9.29") (pinfunction "GPIO_121_P9.29") (pintype "bidirectional"))
    )
    (net (code "72") (name "SPI1_MOSI") (class "Default")
      (node (ref "J1") (pin "4") (pinfunction "4_4") (pintype "passive"))
      (node (ref "U$2") (pin "P9.30") (pinfunction "GPIO_122_P9.30") (pintype "bidirectional"))
    )
    (net (code "73") (name "SPI1_SCLK") (class "Default")
      (node (ref "J1") (pin "3") (pinfunction "3_3") (pintype "passive"))
      (node (ref "U$2") (pin "P9.31") (pinfunction "GPIO_120_P9.31") (pintype "bidirectional"))
    )
    (net (code "74") (name "UART1_RX") (class "Default")
      (node (ref "R15") (pin "2") (pinfunction "2_2") (pintype "passive"))
      (node (ref "U$2") (pin "P9.26") (pinfunction "GPIO_14_P9.26") (pintype "bidirectional"))
    )
    (net (code "75") (name "UART1_TX") (class "Default")
      (node (ref "R14") (pin "2") (pinfunction "2_2") (pintype "passive"))
      (node (ref "U$2") (pin "P9.24") (pinfunction "GPIO_15_P9.24") (pintype "bidirectional"))
    )
    (net (code "76") (name "UART2_RX") (class "Default")
      (node (ref "U$2") (pin "P9.22") (pinfunction "GPIO_2_P9.22") (pintype "bidirectional"))
    )
    (net (code "77") (name "UART2_TX") (class "Default")
      (node (ref "U$2") (pin "P9.21") (pinfunction "GPIO_3_P9.21") (pintype "bidirectional"))
    )
    (net (code "78") (name "UART4_RX") (class "Default")
      (node (ref "R9") (pin "2") (pinfunction "2_2") (pintype "passive"))
      (node (ref "U$2") (pin "P9.11") (pinfunction "GPIO_30_P9.11") (pintype "bidirectional"))
    )
    (net (code "79") (name "UART4_TX") (class "Default")
      (node (ref "R10") (pin "2") (pinfunction "2_2") (pintype "passive"))
      (node (ref "U$2") (pin "P9.13") (pinfunction "GPIO_31_P9.13") (pintype "bidirectional"))
    )
    (net (code "80") (name "UART5_RX") (class "Default")
      (node (ref "J10") (pin "5") (pinfunction "5_5") (pintype "passive"))
      (node (ref "U$2") (pin "P8.38") (pinfunction "GPIO_79_P8.38") (pintype "bidirectional"))
    )
    (net (code "81") (name "UART5_TX") (class "Default")
      (node (ref "J10") (pin "4") (pinfunction "4_4") (pintype "passive"))
      (node (ref "U$2") (pin "P8.37") (pinfunction "GPIO_78_P8.37") (pintype "bidirectional"))
    )
    (net (code "82") (name "US_EN1") (class "Default")
      (node (ref "U$3") (pin "29") (pinfunction "PF1_29") (pintype "bidirectional"))
      (node (ref "U3") (pin "1") (pinfunction "1,2EN_1") (pintype "input"))
    )
    (net (code "83") (name "US_EN2") (class "Default")
      (node (ref "U$3") (pin "31") (pinfunction "PF3_31") (pintype "bidirectional"))
      (node (ref "U3") (pin "9") (pinfunction "3,4EN_9") (pintype "input"))
    )
    (net (code "84") (name "US_PWM1") (class "Default")
      (node (ref "IC1") (pin "1") (pinfunction "I_1") (pintype "input"))
      (node (ref "IC1") (pin "5") (pinfunction "I_5") (pintype "input"))
      (node (ref "U$3") (pin "28") (pinfunction "PF0_28") (pintype "bidirectional"))
    )
    (net (code "85") (name "US_PWM2") (class "Default")
      (node (ref "IC1") (pin "13") (pinfunction "I_13") (pintype "input"))
      (node (ref "IC1") (pin "9") (pinfunction "I_9") (pintype "input"))
      (node (ref "U$3") (pin "30") (pinfunction "PF2_30") (pintype "bidirectional"))
    )
    (net (code "86") (name "VBAT") (class "Default")
      (node (ref "J4") (pin "1") (pinfunction "1_1") (pintype "bidirectional"))
      (node (ref "R1") (pin "2") (pinfunction "2_2") (pintype "passive"))
    )
    (net (code "87") (name "VBAT_SENSE") (class "Default")
      (node (ref "C7") (pin "1") (pinfunction "1_1") (pintype "passive"))
      (node (ref "D1") (pin "C") (pinfunction "C_C") (pintype "passive"))
      (node (ref "R1") (pin "1") (pinfunction "1_1") (pintype "passive"))
      (node (ref "R2") (pin "2") (pinfunction "2_2") (pintype "passive"))
      (node (ref "U$2") (pin "P9.39") (pinfunction "AIN0_P9.39") (pintype "bidirectional"))
    )
    (net (code "88") (name "VDDC") (class "Default")
      (node (ref "C1") (pin "1") (pinfunction "1_1") (pintype "passive"))
      (node (ref "C2") (pin "1") (pinfunction "1_1") (pintype "passive"))
      (node (ref "C8") (pin "1") (pinfunction "1_1") (pintype "passive"))
      (node (ref "C9") (pin "1") (pinfunction "1_1") (pintype "passive"))
      (node (ref "U$3") (pin "25") (pinfunction "VDDC_25") (pintype "bidirectional"))
      (node (ref "U$3") (pin "56") (pinfunction "VDDC2_56") (pintype "bidirectional"))
    )
    (net (code "89") (name "unconnected-(E1-KEY-Pad23)") (class "Default")
      (node (ref "E1") (pin "23") (pinfunction "KEY_23") (pintype "bidirectional"))
    )
    (net (code "90") (name "unconnected-(E1-LED-Pad24)") (class "Default")
      (node (ref "E1") (pin "24") (pinfunction "LED_24") (pintype "bidirectional"))
    )
    (net (code "91") (name "unconnected-(E1-NC5-Pad5)") (class "Default")
      (node (ref "E1") (pin "5") (pinfunction "NC5_5") (pintype "bidirectional"))
    )
    (net (code "92") (name "unconnected-(E1-NC6-Pad6)") (class "Default")
      (node (ref "E1") (pin "6") (pinfunction "NC6_6") (pintype "bidirectional"))
    )
    (net (code "93") (name "unconnected-(E1-NC7-Pad$7)") (class "Default")
      (node (ref "E1") (pin "$7") (pinfunction "NC7_$7") (pintype "bidirectional"))
    )
    (net (code "94") (name "unconnected-(E1-NC8-Pad8)") (class "Default")
      (node (ref "E1") (pin "8") (pinfunction "NC8_8") (pintype "bidirectional"))
    )
    (net (code "95") (name "unconnected-(E1-NC9-Pad9)") (class "Default")
      (node (ref "E1") (pin "9") (pinfunction "NC9_9") (pintype "bidirectional"))
    )
    (net (code "96") (name "unconnected-(E1-NC10-Pad10)") (class "Default")
      (node (ref "E1") (pin "10") (pinfunction "NC10_10") (pintype "bidirectional"))
    )
    (net (code "97") (name "unconnected-(E1-NC16-Pad16)") (class "Default")
      (node (ref "E1") (pin "16") (pinfunction "NC16_16") (pintype "bidirectional"))
    )
    (net (code "98") (name "unconnected-(E1-NC17-Pad17)") (class "Default")
      (node (ref "E1") (pin "17") (pinfunction "NC17_17") (pintype "bidirectional"))
    )
    (net (code "99") (name "unconnected-(E1-NC18-Pad18)") (class "Default")
      (node (ref "E1") (pin "18") (pinfunction "NC18_18") (pintype "bidirectional"))
    )
    (net (code "100") (name "unconnected-(E1-NC19-Pad19)") (class "Default")
      (node (ref "E1") (pin "19") (pinfunction "NC19_19") (pintype "bidirectional"))
    )
    (net (code "101") (name "unconnected-(E1-PIO2-Pad25)") (class "Default")
      (node (ref "E1") (pin "25") (pinfunction "PIO2_25") (pintype "bidirectional"))
    )
    (net (code "102") (name "unconnected-(E1-PIO3-Pad26)") (class "Default")
      (node (ref "E1") (pin "26") (pinfunction "PIO3_26") (pintype "bidirectional"))
    )
    (net (code "103") (name "unconnected-(E1-PIO4-Pad27)") (class "Default")
      (node (ref "E1") (pin "27") (pinfunction "PIO4_27") (pintype "bidirectional"))
    )
    (net (code "104") (name "unconnected-(E1-PIO5-Pad28)") (class "Default")
      (node (ref "E1") (pin "28") (pinfunction "PIO5_28") (pintype "bidirectional"))
    )
    (net (code "105") (name "unconnected-(E1-PIO6-Pad29)") (class "Default")
      (node (ref "E1") (pin "29") (pinfunction "PIO6_29") (pintype "bidirectional"))
    )
    (net (code "106") (name "unconnected-(E1-PIO7-Pad30)") (class "Default")
      (node (ref "E1") (pin "30") (pinfunction "PIO7_30") (pintype "bidirectional"))
    )
    (net (code "107") (name "unconnected-(E1-PIO8-Pad31)") (class "Default")
      (node (ref "E1") (pin "31") (pinfunction "PIO8_31") (pintype "bidirectional"))
    )
    (net (code "108") (name "unconnected-(E1-PIO9-Pad32)") (class "Default")
      (node (ref "E1") (pin "32") (pinfunction "PIO9_32") (pintype "bidirectional"))
    )
    (net (code "109") (name "unconnected-(E1-PIO10-Pad33)") (class "Default")
      (node (ref "E1") (pin "33") (pinfunction "PIO10_33") (pintype "bidirectional"))
    )
    (net (code "110") (name "unconnected-(E1-PIO11-Pad34)") (class "Default")
      (node (ref "E1") (pin "34") (pinfunction "PIO11_34") (pintype "bidirectional"))
    )
    (net (code "111") (name "unconnected-(E1-RESET-Pad11)") (class "Default")
      (node (ref "E1") (pin "11") (pinfunction "RESET_11") (pintype "bidirectional"))
    )
    (net (code "112") (name "unconnected-(E1-UART_CTS-Pad3)") (class "Default")
      (node (ref "E1") (pin "3") (pinfunction "UART_CTS_3") (pintype "bidirectional"))
    )
    (net (code "113") (name "unconnected-(E1-UART_RTS-Pad4)") (class "Default")
      (node (ref "E1") (pin "4") (pinfunction "UART_RTS_4") (pintype "bidirectional"))
    )
    (net (code "114") (name "unconnected-(E1-USB_D+-Pad20)") (class "Default")
      (node (ref "E1") (pin "20") (pinfunction "USB_D+_20") (pintype "bidirectional"))
    )
    (net (code "115") (name "unconnected-(E1-USB_D--Pad15)") (class "Default")
      (node (ref "E1") (pin "15") (pinfunction "USB_D-_15") (pintype "bidirectional"))
    )
    (net (code "116") (name "unconnected-(J1-Pad5)") (class "Default")
      (node (ref "J1") (pin "5") (pinfunction "5_5") (pintype "passive"))
    )
    (net (code "117") (name "unconnected-(J1-Pad6)") (class "Default")
      (node (ref "J1") (pin "6") (pinfunction "6_6") (pintype "passive"))
    )
    (net (code "118") (name "unconnected-(J8-Pad2)") (class "Default")
      (node (ref "J8") (pin "2") (pinfunction "2_2") (pintype "passive"))
    )
    (net (code "119") (name "unconnected-(J8-Pad3)") (class "Default")
      (node (ref "J8") (pin "3") (pinfunction "3_3") (pintype "passive"))
    )
    (net (code "120") (name "unconnected-(J9-Pad2)") (class "Default")
      (node (ref "J9") (pin "2") (pinfunction "2_2") (pintype "passive"))
    )
    (net (code "121") (name "unconnected-(J9-Pad3)") (class "Default")
      (node (ref "J9") (pin "3") (pinfunction "3_3") (pintype "passive"))
    )
    (net (code "122") (name "unconnected-(U$2A-GPIO_8-PadP8.35)") (class "Default")
      (node (ref "U$2") (pin "P8.35") (pinfunction "GPIO_8_P8.35") (pintype "bidirectional"))
    )
    (net (code "123") (name "unconnected-(U$2A-GPIO_9-PadP8.33)") (class "Default")
      (node (ref "U$2") (pin "P8.33") (pinfunction "GPIO_9_P8.33") (pintype "bidirectional"))
    )
    (net (code "124") (name "unconnected-(U$2A-GPIO_10-PadP8.31)") (class "Default")
      (node (ref "U$2") (pin "P8.31") (pinfunction "GPIO_10_P8.31") (pintype "bidirectional"))
    )
    (net (code "125") (name "unconnected-(U$2A-GPIO_22-PadP8.19)") (class "Default")
      (node (ref "U$2") (pin "P8.19") (pinfunction "GPIO_22_P8.19") (pintype "bidirectional"))
    )
    (net (code "126") (name "unconnected-(U$2A-GPIO_23-PadP8.13)") (class "Default")
      (node (ref "U$2") (pin "P8.13") (pinfunction "GPIO_23_P8.13") (pintype "bidirectional"))
    )
    (net (code "127") (name "unconnected-(U$2A-GPIO_26-PadP8.14)") (class "Default")
      (node (ref "U$2") (pin "P8.14") (pinfunction "GPIO_26_P8.14") (pintype "bidirectional"))
    )
    (net (code "128") (name "unconnected-(U$2A-GPIO_27-PadP8.17)") (class "Default")
      (node (ref "U$2") (pin "P8.17") (pinfunction "GPIO_27_P8.17") (pintype "bidirectional"))
    )
    (net (code "129") (name "unconnected-(U$2A-GPIO_32-PadP8.25)") (class "Default")
      (node (ref "U$2") (pin "P8.25") (pinfunction "GPIO_32_P8.25") (pintype "bidirectional"))
    )
    (net (code "130") (name "unconnected-(U$2A-GPIO_33-PadP8.24)") (class "Default")
      (node (ref "U$2") (pin "P8.24") (pinfunction "GPIO_33_P8.24") (pintype "bidirectional"))
    )
    (net (code "131") (name "unconnected-(U$2A-GPIO_34-PadP8.5)") (class "Default")
      (node (ref "U$2") (pin "P8.5") (pinfunction "GPIO_34_P8.5") (pintype "bidirectional"))
    )
    (net (code "132") (name "unconnected-(U$2A-GPIO_35-PadP8.6)") (class "Default")
      (node (ref "U$2") (pin "P8.6") (pinfunction "GPIO_35_P8.6") (pintype "bidirectional"))
    )
    (net (code "133") (name "unconnected-(U$2A-GPIO_36-PadP8.23)") (class "Default")
      (node (ref "U$2") (pin "P8.23") (pinfunction "GPIO_36_P8.23") (pintype "bidirectional"))
    )
    (net (code "134") (name "unconnected-(U$2A-GPIO_37-PadP8.22)") (class "Default")
      (node (ref "U$2") (pin "P8.22") (pinfunction "GPIO_37_P8.22") (pintype "bidirectional"))
    )
    (net (code "135") (name "unconnected-(U$2A-GPIO_38-PadP8.3)") (class "Default")
      (node (ref "U$2") (pin "P8.3") (pinfunction "GPIO_38_P8.3") (pintype "bidirectional"))
    )
    (net (code "136") (name "unconnected-(U$2A-GPIO_39-PadP8.4)") (class "Default")
      (node (ref "U$2") (pin "P8.4") (pinfunction "GPIO_39_P8.4") (pintype "bidirectional"))
    )
    (net (code "137") (name "unconnected-(U$2A-GPIO_44-PadP8.12)") (class "Default")
      (node (ref "U$2") (pin "P8.12") (pinfunction "GPIO_44_P8.12") (pintype "bidirectional"))
    )
    (net (code "138") (name "unconnected-(U$2A-GPIO_46-PadP8.16)") (class "Default")
      (node (ref "U$2") (pin "P8.16") (pinfunction "GPIO_46_P8.16") (pintype "bidirectional"))
    )
    (net (code "139") (name "unconnected-(U$2A-GPIO_61-PadP8.26)") (class "Default")
      (node (ref "U$2") (pin "P8.26") (pinfunction "GPIO_61_P8.26") (pintype "bidirectional"))
    )
    (net (code "140") (name "unconnected-(U$2A-GPIO_62-PadP8.21)") (class "Default")
      (node (ref "U$2") (pin "P8.21") (pinfunction "GPIO_62_P8.21") (pintype "bidirectional"))
    )
    (net (code "141") (name "unconnected-(U$2A-GPIO_63-PadP8.20)") (class "Default")
      (node (ref "U$2") (pin "P8.20") (pinfunction "GPIO_63_P8.20") (pintype "bidirectional"))
    )
    (net (code "142") (name "unconnected-(U$2A-GPIO_65-PadP8.18)") (class "Default")
      (node (ref "U$2") (pin "P8.18") (pinfunction "GPIO_65_P8.18") (pintype "bidirectional"))
    )
    (net (code "143") (name "unconnected-(U$2A-GPIO_67-PadP8.8)") (class "Default")
      (node (ref "U$2") (pin "P8.8") (pinfunction "GPIO_67_P8.8") (pintype "bidirectional"))
    )
    (net (code "144") (name "unconnected-(U$2A-GPIO_68-PadP8.10)") (class "Default")
      (node (ref "U$2") (pin "P8.10") (pinfunction "GPIO_68_P8.10") (pintype "bidirectional"))
    )
    (net (code "145") (name "unconnected-(U$2A-GPIO_70-PadP8.45)") (class "Default")
      (node (ref "U$2") (pin "P8.45") (pinfunction "GPIO_70_P8.45") (pintype "bidirectional"))
    )
    (net (code "146") (name "unconnected-(U$2A-GPIO_71-PadP8.46)") (class "Default")
      (node (ref "U$2") (pin "P8.46") (pinfunction "GPIO_71_P8.46") (pintype "bidirectional"))
    )
    (net (code "147") (name "unconnected-(U$2A-GPIO_72-PadP8.43)") (class "Default")
      (node (ref "U$2") (pin "P8.43") (pinfunction "GPIO_72_P8.43") (pintype "bidirectional"))
    )
    (net (code "148") (name "unconnected-(U$2A-GPIO_73-PadP8.44)") (class "Default")
      (node (ref "U$2") (pin "P8.44") (pinfunction "GPIO_73_P8.44") (pintype "bidirectional"))
    )
    (net (code "149") (name "unconnected-(U$2A-GPIO_80-PadP8.36)") (class "Default")
      (node (ref "U$2") (pin "P8.36") (pinfunction "GPIO_80_P8.36") (pintype "bidirectional"))
    )
    (net (code "150") (name "unconnected-(U$2A-GPIO_81-PadP8.34)") (class "Default")
      (node (ref "U$2") (pin "P8.34") (pinfunction "GPIO_81_P8.34") (pintype "bidirectional"))
    )
    (net (code "151") (name "unconnected-(U$2B-AIN1-PadP9.40)") (class "Default")
      (node (ref "U$2") (pin "P9.40") (pinfunction "AIN1_P9.40") (pintype "bidirectional"))
    )
    (net (code "152") (name "unconnected-(U$2B-AIN2-PadP9.37)") (class "Default")
      (node (ref "U$2") (pin "P9.37") (pinfunction "AIN2_P9.37") (pintype "bidirectional"))
    )
    (net (code "153") (name "unconnected-(U$2B-AIN3-PadP9.38)") (class "Default")
      (node (ref "U$2") (pin "P9.38") (pinfunction "AIN3_P9.38") (pintype "bidirectional"))
    )
    (net (code "154") (name "unconnected-(U$2B-AIN4-PadP9.33)") (class "Default")
      (node (ref "U$2") (pin "P9.33") (pinfunction "AIN4_P9.33") (pintype "bidirectional"))
    )
    (net (code "155") (name "unconnected-(U$2B-AIN5-PadP9.36)") (class "Default")
      (node (ref "U$2") (pin "P9.36") (pinfunction "AIN5_P9.36") (pintype "bidirectional"))
    )
    (net (code "156") (name "unconnected-(U$2B-AIN6-PadP9.35)") (class "Default")
      (node (ref "U$2") (pin "P9.35") (pinfunction "AIN6_P9.35") (pintype "bidirectional"))
    )
    (net (code "157") (name "unconnected-(U$2B-DGND-PadP9.43)") (class "Default")
      (node (ref "U$2") (pin "P9.43") (pinfunction "DGND_P9.43") (pintype "bidirectional"))
    )
    (net (code "158") (name "unconnected-(U$2B-DGND-PadP9.44)") (class "Default")
      (node (ref "U$2") (pin "P9.44") (pinfunction "DGND_P9.44") (pintype "bidirectional"))
    )
    (net (code "159") (name "unconnected-(U$2B-DGND-PadP9.45)") (class "Default")
      (node (ref "U$2") (pin "P9.45") (pinfunction "DGND_P9.45") (pintype "bidirectional"))
    )
    (net (code "160") (name "unconnected-(U$2B-DGND-PadP9.46)") (class "Default")
      (node (ref "U$2") (pin "P9.46") (pinfunction "DGND_P9.46") (pintype "bidirectional"))
    )
    (net (code "161") (name "unconnected-(U$2B-GNDA_ADC-PadP9.34)") (class "Default")
      (node (ref "U$2") (pin "P9.34") (pinfunction "GNDA_ADC_P9.34") (pintype "bidirectional"))
    )
    (net (code "162") (name "unconnected-(U$2B-GPIO_20-PadP9.41)") (class "Default")
      (node (ref "U$2") (pin "P9.41") (pinfunction "GPIO_20_P9.41") (pintype "bidirectional"))
    )
    (net (code "163") (name "unconnected-(U$2B-GPIO_40-PadP9.14)") (class "Default")
      (node (ref "U$2") (pin "P9.14") (pinfunction "GPIO_40_P9.14") (pintype "bidirectional"))
    )
    (net (code "164") (name "unconnected-(U$2B-GPIO_48-PadP9.15)") (class "Default")
      (node (ref "U$2") (pin "P9.15") (pinfunction "GPIO_48_P9.15") (pintype "bidirectional"))
    )
    (net (code "165") (name "unconnected-(U$2B-GPIO_49-PadP9.23)") (class "Default")
      (node (ref "U$2") (pin "P9.23") (pinfunction "GPIO_49_P9.23") (pintype "bidirectional"))
    )
    (net (code "166") (name "unconnected-(U$2B-GPIO_51-PadP9.16)") (class "Default")
      (node (ref "U$2") (pin "P9.16") (pinfunction "GPIO_51_P9.16") (pintype "bidirectional"))
    )
    (net (code "167") (name "unconnected-(U$2B-GPIO_60-PadP9.12)") (class "Default")
      (node (ref "U$2") (pin "P9.12") (pinfunction "GPIO_60_P9.12") (pintype "bidirectional"))
    )
    (net (code "168") (name "unconnected-(U$2B-GPIO_125-PadP9.27)") (class "Default")
      (node (ref "U$2") (pin "P9.27") (pinfunction "GPIO_125_P9.27") (pintype "bidirectional"))
    )
    (net (code "169") (name "unconnected-(U$2B-PWR_BUT-PadP9.9)") (class "Default")
      (node (ref "U$2") (pin "P9.9") (pinfunction "PWR_BUT_P9.9") (pintype "bidirectional"))
    )
    (net (code "170") (name "unconnected-(U$2B-SYS_5V-PadP9.7)") (class "Default")
      (node (ref "U$2") (pin "P9.7") (pinfunction "SYS_5V_P9.7") (pintype "bidirectional"))
    )
    (net (code "171") (name "unconnected-(U$2B-SYS_5V-PadP9.8)") (class "Default")
      (node (ref "U$2") (pin "P9.8") (pinfunction "SYS_5V_P9.8") (pintype "bidirectional"))
    )
    (net (code "172") (name "unconnected-(U$2B-SYS_RESET~{N}-PadP9.10)") (class "Default")
      (node (ref "U$2") (pin "P9.10") (pinfunction "SYS_RESET~{N}_P9.10") (pintype "bidirectional"))
    )
    (net (code "173") (name "unconnected-(U$2B-VDD_ADC-PadP9.32)") (class "Default")
      (node (ref "U$2") (pin "P9.32") (pinfunction "VDD_ADC_P9.32") (pintype "bidirectional"))
    )
    (net (code "174") (name "unconnected-(U$3-HIB-Pad33)") (class "Default")
      (node (ref "U$3") (pin "33") (pinfunction "HIB_33") (pintype "bidirectional"))
    )
    (net (code "175") (name "unconnected-(U$3-PA2-Pad19)") (class "Default")
      (node (ref "U$3") (pin "19") (pinfunction "PA2_19") (pintype "bidirectional"))
    )
    (net (code "176") (name "unconnected-(U$3-PA3-Pad20)") (class "Default")
      (node (ref "U$3") (pin "20") (pinfunction "PA3_20") (pintype "bidirectional"))
    )
    (net (code "177") (name "unconnected-(U$3-PA4-Pad21)") (class "Default")
      (node (ref "U$3") (pin "21") (pinfunction "PA4_21") (pintype "bidirectional"))
    )
    (net (code "178") (name "unconnected-(U$3-PA5-Pad22)") (class "Default")
      (node (ref "U$3") (pin "22") (pinfunction "PA5_22") (pintype "bidirectional"))
    )
    (net (code "179") (name "unconnected-(U$3-PB3-Pad48)") (class "Default")
      (node (ref "U$3") (pin "48") (pinfunction "PB3_48") (pintype "bidirectional"))
    )
    (net (code "180") (name "unconnected-(U$3-PC4-Pad16)") (class "Default")
      (node (ref "U$3") (pin "16") (pinfunction "PC4_16") (pintype "bidirectional"))
    )
    (net (code "181") (name "unconnected-(U$3-PC5-Pad15)") (class "Default")
      (node (ref "U$3") (pin "15") (pinfunction "PC5_15") (pintype "bidirectional"))
    )
    (net (code "182") (name "unconnected-(U$3-PC6-Pad14)") (class "Default")
      (node (ref "U$3") (pin "14") (pinfunction "PC6_14") (pintype "bidirectional"))
    )
    (net (code "183") (name "unconnected-(U$3-PC7-Pad13)") (class "Default")
      (node (ref "U$3") (pin "13") (pinfunction "PC7_13") (pintype "bidirectional"))
    )
    (net (code "184") (name "unconnected-(U$3-PD2-Pad63)") (class "Default")
      (node (ref "U$3") (pin "63") (pinfunction "PD2_63") (pintype "bidirectional"))
    )
    (net (code "185") (name "unconnected-(U$3-PD3-Pad64)") (class "Default")
      (node (ref "U$3") (pin "64") (pinfunction "PD3_64") (pintype "bidirectional"))
    )
    (net (code "186") (name "unconnected-(U$3-PD4-Pad43)") (class "Default")
      (node (ref "U$3") (pin "43") (pinfunction "PD4_43") (pintype "bidirectional"))
    )
    (net (code "187") (name "unconnected-(U$3-PD5-Pad44)") (class "Default")
      (node (ref "U$3") (pin "44") (pinfunction "PD5_44") (pintype "bidirectional"))
    )
    (net (code "188") (name "unconnected-(U$3-PD6-Pad53)") (class "Default")
      (node (ref "U$3") (pin "53") (pinfunction "PD6_53") (pintype "bidirectional"))
    )
    (net (code "189") (name "unconnected-(U$3-PD7-Pad10)") (class "Default")
      (node (ref "U$3") (pin "10") (pinfunction "PD7_10") (pintype "bidirectional"))
    )
    (net (code "190") (name "unconnected-(U$3-PE1-Pad8)") (class "Default")
      (node (ref "U$3") (pin "8") (pinfunction "PE1_8") (pintype "bidirectional"))
    )
    (net (code "191") (name "unconnected-(U$3-PE2-Pad7)") (class "Default")
      (node (ref "U$3") (pin "7") (pinfunction "PE2_7") (pintype "bidirectional"))
    )
    (net (code "192") (name "unconnected-(U$3-PE3-Pad6)") (class "Default")
      (node (ref "U$3") (pin "6") (pinfunction "PE3_6") (pintype "bidirectional"))
    )
    (net (code "193") (name "unconnected-(U$3-PF4-Pad5)") (class "Default")
      (node (ref "U$3") (pin "5") (pinfunction "PF4_5") (pintype "bidirectional"))
    )
    (net (code "194") (name "unconnected-(U$3-XOSC1-Pad36)") (class "Default")
      (node (ref "U$3") (pin "36") (pinfunction "XOSC1_36") (pintype "bidirectional"))
    )
    (net (code "195") (name "unconnected-(U2-P$1-Pad1)") (class "Default")
      (node (ref "U2") (pin "1") (pinfunction "P$1_1") (pintype "bidirectional"))
    )
    (net (code "196") (name "unconnected-(U2-P$2-Pad2)") (class "Default")
      (node (ref "U2") (pin "2") (pinfunction "P$2_2") (pintype "bidirectional"))
    )
    (net (code "197") (name "unconnected-(U2-P$3-Pad3)") (class "Default")
      (node (ref "U2") (pin "3") (pinfunction "P$3_3") (pintype "bidirectional"))
    )
    (net (code "198") (name "unconnected-(U2-P$4-Pad4)") (class "Default")
      (node (ref "U2") (pin "4") (pinfunction "P$4_4") (pintype "bidirectional"))
    )
    (net (code "199") (name "unconnected-(U2-P$5-Pad5)") (class "Default")
      (node (ref "U2") (pin "5") (pinfunction "P$5_5") (pintype "bidirectional"))
    )
    (net (code "200") (name "unconnected-(U2-P$6-Pad6)") (class "Default")
      (node (ref "U2") (pin "6") (pinfunction "P$6_6") (pintype "bidirectional"))
    )
    (net (code "201") (name "unconnected-(U2-P$7-Pad7)") (class "Default")
      (node (ref "U2") (pin "7") (pinfunction "P$7_7") (pintype "bidirectional"))
    )
    (net (code "202") (name "unconnected-(U2-P$15-Pad15)") (class "Default")
      (node (ref "U2") (pin "15") (pinfunction "P$15_15") (pintype "bidirectional"))
    )
    (net (code "203") (name "unconnected-(U2-P$16-Pad16)") (class "Default")
      (node (ref "U2") (pin "16") (pinfunction "P$16_16") (pintype "bidirectional"))
    )
    (net (code "204") (name "unconnected-(U2-P$19-Pad19)") (class "Default")
      (node (ref "U2") (pin "19") (pinfunction "P$19_19") (pintype "bidirectional"))
    )
    (net (code "205") (name "unconnected-(U2-P$20-Pad20)") (class "Default")
      (node (ref "U2") (pin "20") (pinfunction "P$20_20") (pintype "bidirectional"))
    )
    (net (code "206") (name "unconnected-(U2-P$21-Pad21)") (class "Default")
      (node (ref "U2") (pin "21") (pinfunction "P$21_21") (pintype "bidirectional"))
    )
    (net (code "207") (name "unconnected-(U2-P$22-Pad22)") (class "Default")
      (node (ref "U2") (pin "22") (pinfunction "P$22_22") (pintype "bidirectional"))
    )
    (net (code "208") (name "unconnected-(U2-P$23-Pad23)") (class "Default")
      (node (ref "U2") (pin "23") (pinfunction "P$23_23") (pintype "bidirectional"))
    )
    (net (code "209") (name "unconnected-(U2-P$24-Pad24)") (class "Default")
      (node (ref "U2") (pin "24") (pinfunction "P$24_24") (pintype "bidirectional"))
    )
  )
)
